# Net4CPC.net
KiCad netlist of a schematic drawn in EAGLE
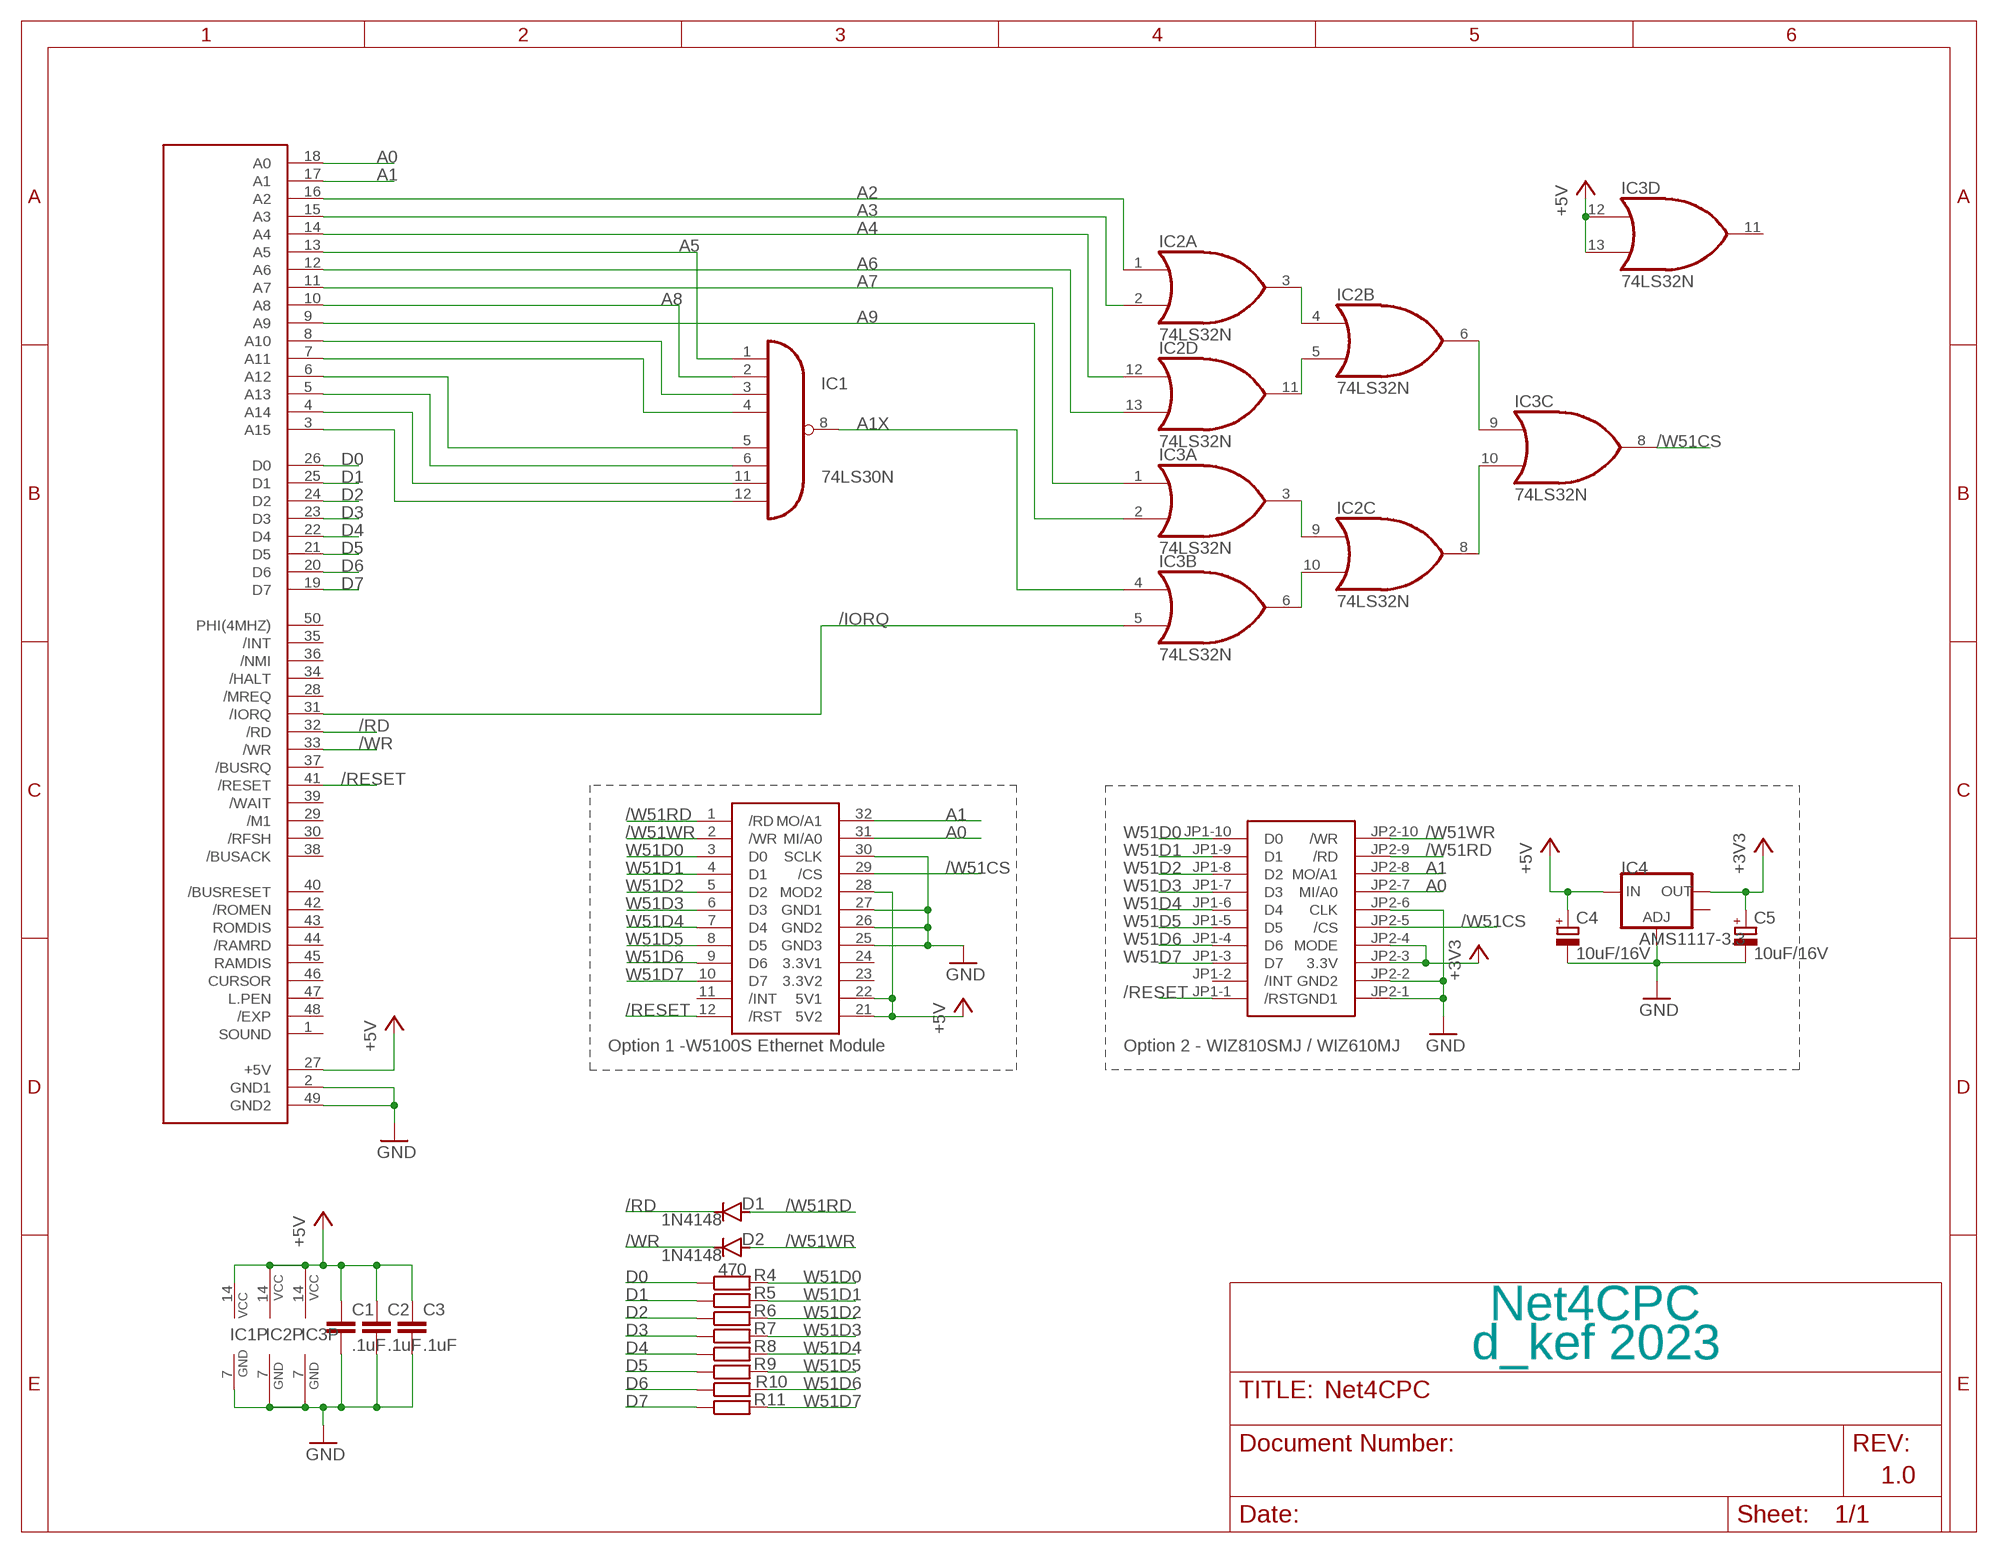
[diagram p0: schematic, sheet 1]

(export (version "E")
  (design (tool "Eeschema 10.0.6"))
  (components
    (comp (ref "C1")
      (value ".1uF")
      (footprint "eagle-import:C025-025X050")
      (libsource (lib "eagle-import") (part "C-EU025-025X050"))
    )
    (comp (ref "C2")
      (value ".1uF")
      (footprint "eagle-import:C025-025X050")
      (libsource (lib "eagle-import") (part "C-EU025-025X050"))
    )
    (comp (ref "C3")
      (value ".1uF")
      (footprint "eagle-import:C025-025X050")
      (libsource (lib "eagle-import") (part "C-EU025-025X050"))
    )
    (comp (ref "C4")
      (value "10uF/16V")
      (footprint "eagle-import:E5-6")
      (libsource (lib "eagle-import") (part "CPOL-EUE5-6"))
    )
    (comp (ref "C5")
      (value "10uF/16V")
      (footprint "eagle-import:E5-6")
      (libsource (lib "eagle-import") (part "CPOL-EUE5-6"))
    )
    (comp (ref "CON1")
      (value "CPCBUS")
      (footprint "eagle-import:2X25")
      (libsource (lib "eagle-import") (part "AMSTRAD_CPC_BUSP"))
    )
    (comp (ref "D1")
      (value "1N4148")
      (footprint "eagle-import:DO35-7")
      (libsource (lib "eagle-import") (part "1N4148DO35-7"))
    )
    (comp (ref "D2")
      (value "1N4148")
      (footprint "eagle-import:DO35-7")
      (libsource (lib "eagle-import") (part "1N4148DO35-7"))
    )
    (comp (ref "IC1")
      (value "74LS30N")
      (footprint "eagle-import:DIL14")
      (libsource (lib "eagle-import") (part "7430NHCT"))
    )
    (comp (ref "IC2")
      (value "74LS32N")
      (footprint "eagle-import:DIL14")
      (libsource (lib "eagle-import") (part "7432NLS"))
    )
    (comp (ref "IC3")
      (value "74LS32N")
      (footprint "eagle-import:DIL14")
      (libsource (lib "eagle-import") (part "7432NLS"))
    )
    (comp (ref "IC4")
      (value "AMS1117-3.3")
      (footprint "eagle-import:SOT223")
      (libsource (lib "eagle-import") (part "V_REG_LM1117SOT223"))
    )
    (comp (ref "R4")
      (value "470")
      (footprint "eagle-import:0204_7")
      (libsource (lib "eagle-import") (part "R-EU_0204/7"))
    )
    (comp (ref "R5")
      (value "470")
      (footprint "eagle-import:0204_7")
      (libsource (lib "eagle-import") (part "R-EU_0204/7"))
    )
    (comp (ref "R6")
      (value "470")
      (footprint "eagle-import:0204_7")
      (libsource (lib "eagle-import") (part "R-EU_0204/7"))
    )
    (comp (ref "R7")
      (value "470")
      (footprint "eagle-import:0204_7")
      (libsource (lib "eagle-import") (part "R-EU_0204/7"))
    )
    (comp (ref "R8")
      (value "470")
      (footprint "eagle-import:0204_7")
      (libsource (lib "eagle-import") (part "R-EU_0204/7"))
    )
    (comp (ref "R9")
      (value "470")
      (footprint "eagle-import:0204_7")
      (libsource (lib "eagle-import") (part "R-EU_0204/7"))
    )
    (comp (ref "R10")
      (value "470")
      (footprint "eagle-import:0204_7")
      (libsource (lib "eagle-import") (part "R-EU_0204/7"))
    )
    (comp (ref "R11")
      (value "470")
      (footprint "eagle-import:0204_7")
      (libsource (lib "eagle-import") (part "R-EU_0204/7"))
    )
    (comp (ref "W5100S-MODULE")
      (value "W5100S-NETWORK-MODULENO-NAMES")
      (footprint "eagle-import:W5100S-NETWORK-MODULE-NO-NAMES")
      (libsource (lib "eagle-import") (part "W5100S-NETWORK-MODULENO-NAMES"))
    )
    (comp (ref "WIZ810SMJ")
      (value "WIZ810SMJ-NETWORK-MODULENO-NAMES")
      (footprint "eagle-import:WIZ810SMJ-NETWORK-MODULE-NO-NAMES")
      (libsource (lib "eagle-import") (part "WIZ810SMJ-NETWORK-MODULENO-NAMES"))
    )
  )
  (nets
    (net (code "1") (name "+3V3") (class "Default")
      (node (ref "C5") (pin "+") (pinfunction "+_+") (pintype "passive"))
      (node (ref "IC4") (pin "2") (pinfunction "OUT_2") (pintype "output"))
      (node (ref "WIZ810SMJ") (pin "JP2-3") (pinfunction "3.3V_JP2-3") (pintype "power_in"))
      (node (ref "WIZ810SMJ") (pin "JP2-4") (pinfunction "MODE_JP2-4") (pintype "passive"))
    )
    (net (code "2") (name "+5V") (class "Default")
      (node (ref "C1") (pin "1") (pinfunction "1_1") (pintype "passive"))
      (node (ref "C2") (pin "1") (pinfunction "1_1") (pintype "passive"))
      (node (ref "C3") (pin "1") (pinfunction "1_1") (pintype "passive"))
      (node (ref "C4") (pin "+") (pinfunction "+_+") (pintype "passive"))
      (node (ref "CON1") (pin "27") (pinfunction "+5V_27") (pintype "bidirectional"))
      (node (ref "IC1") (pin "14") (pinfunction "VCC_14") (pintype "power_in"))
      (node (ref "IC2") (pin "14") (pinfunction "VCC_14") (pintype "power_in"))
      (node (ref "IC3") (pin "12") (pinfunction "I0_12") (pintype "input"))
      (node (ref "IC3") (pin "13") (pinfunction "I1_13") (pintype "input"))
      (node (ref "IC3") (pin "14") (pinfunction "VCC_14") (pintype "power_in"))
      (node (ref "IC4") (pin "3") (pinfunction "IN_3") (pintype "input"))
      (node (ref "W5100S-MODULE") (pin "21") (pinfunction "5V2_21") (pintype "power_in"))
      (node (ref "W5100S-MODULE") (pin "22") (pinfunction "5V1_22") (pintype "power_in"))
      (node (ref "W5100S-MODULE") (pin "28") (pinfunction "MOD2_28") (pintype "passive"))
    )
    (net (code "3") (name "/3.3V1") (class "Default")
      (node (ref "W5100S-MODULE") (pin "24") (pinfunction "3.3V1_24") (pintype "power_in"))
    )
    (net (code "4") (name "/3.3V2") (class "Default")
      (node (ref "W5100S-MODULE") (pin "23") (pinfunction "3.3V2_23") (pintype "power_in"))
    )
    (net (code "5") (name "/A0") (class "Default")
      (node (ref "CON1") (pin "18") (pinfunction "A0_18") (pintype "bidirectional"))
      (node (ref "W5100S-MODULE") (pin "31") (pinfunction "MI/A0_31") (pintype "input"))
      (node (ref "WIZ810SMJ") (pin "JP2-7") (pinfunction "MI/A0_JP2-7") (pintype "input"))
    )
    (net (code "6") (name "/A1") (class "Default")
      (node (ref "CON1") (pin "17") (pinfunction "A1_17") (pintype "bidirectional"))
      (node (ref "W5100S-MODULE") (pin "32") (pinfunction "MO/A1_32") (pintype "bidirectional"))
      (node (ref "WIZ810SMJ") (pin "JP2-8") (pinfunction "MO/A1_JP2-8") (pintype "bidirectional"))
    )
    (net (code "7") (name "/A1X") (class "Default")
      (node (ref "IC1") (pin "8") (pinfunction "O_8") (pintype "output"))
      (node (ref "IC3") (pin "4") (pinfunction "I0_4") (pintype "input"))
    )
    (net (code "8") (name "/A2") (class "Default")
      (node (ref "CON1") (pin "16") (pinfunction "A2_16") (pintype "bidirectional"))
      (node (ref "IC2") (pin "1") (pinfunction "I0_1") (pintype "input"))
    )
    (net (code "9") (name "/A3") (class "Default")
      (node (ref "CON1") (pin "15") (pinfunction "A3_15") (pintype "bidirectional"))
      (node (ref "IC2") (pin "2") (pinfunction "I1_2") (pintype "input"))
    )
    (net (code "10") (name "/A4") (class "Default")
      (node (ref "CON1") (pin "14") (pinfunction "A4_14") (pintype "bidirectional"))
      (node (ref "IC2") (pin "12") (pinfunction "I0_12") (pintype "input"))
    )
    (net (code "11") (name "/A5") (class "Default")
      (node (ref "CON1") (pin "13") (pinfunction "A5_13") (pintype "bidirectional"))
      (node (ref "IC1") (pin "1") (pinfunction "I0_1") (pintype "input"))
    )
    (net (code "12") (name "/A6") (class "Default")
      (node (ref "CON1") (pin "12") (pinfunction "A6_12") (pintype "bidirectional"))
      (node (ref "IC2") (pin "13") (pinfunction "I1_13") (pintype "input"))
    )
    (net (code "13") (name "/A7") (class "Default")
      (node (ref "CON1") (pin "11") (pinfunction "A7_11") (pintype "bidirectional"))
      (node (ref "IC3") (pin "1") (pinfunction "I0_1") (pintype "input"))
    )
    (net (code "14") (name "/A8") (class "Default")
      (node (ref "CON1") (pin "10") (pinfunction "A8_10") (pintype "bidirectional"))
      (node (ref "IC1") (pin "2") (pinfunction "I1_2") (pintype "input"))
    )
    (net (code "15") (name "/A9") (class "Default")
      (node (ref "CON1") (pin "9") (pinfunction "A9_9") (pintype "bidirectional"))
      (node (ref "IC3") (pin "2") (pinfunction "I1_2") (pintype "input"))
    )
    (net (code "16") (name "/D0") (class "Default")
      (node (ref "CON1") (pin "26") (pinfunction "D0_26") (pintype "bidirectional"))
      (node (ref "R4") (pin "1") (pinfunction "1_1") (pintype "passive"))
    )
    (net (code "17") (name "/D1") (class "Default")
      (node (ref "CON1") (pin "25") (pinfunction "D1_25") (pintype "bidirectional"))
      (node (ref "R5") (pin "1") (pinfunction "1_1") (pintype "passive"))
    )
    (net (code "18") (name "/D2") (class "Default")
      (node (ref "CON1") (pin "24") (pinfunction "D2_24") (pintype "bidirectional"))
      (node (ref "R6") (pin "1") (pinfunction "1_1") (pintype "passive"))
    )
    (net (code "19") (name "/D3") (class "Default")
      (node (ref "CON1") (pin "23") (pinfunction "D3_23") (pintype "bidirectional"))
      (node (ref "R7") (pin "1") (pinfunction "1_1") (pintype "passive"))
    )
    (net (code "20") (name "/D4") (class "Default")
      (node (ref "CON1") (pin "22") (pinfunction "D4_22") (pintype "bidirectional"))
      (node (ref "R8") (pin "1") (pinfunction "1_1") (pintype "passive"))
    )
    (net (code "21") (name "/D5") (class "Default")
      (node (ref "CON1") (pin "21") (pinfunction "D5_21") (pintype "bidirectional"))
      (node (ref "R9") (pin "1") (pinfunction "1_1") (pintype "passive"))
    )
    (net (code "22") (name "/D6") (class "Default")
      (node (ref "CON1") (pin "20") (pinfunction "D6_20") (pintype "bidirectional"))
      (node (ref "R10") (pin "1") (pinfunction "1_1") (pintype "passive"))
    )
    (net (code "23") (name "/D7") (class "Default")
      (node (ref "CON1") (pin "19") (pinfunction "D7_19") (pintype "bidirectional"))
      (node (ref "R11") (pin "1") (pinfunction "1_1") (pintype "passive"))
    )
    (net (code "24") (name "/W51D0") (class "Default")
      (node (ref "R4") (pin "2") (pinfunction "2_2") (pintype "passive"))
      (node (ref "W5100S-MODULE") (pin "3") (pinfunction "D0_3") (pintype "bidirectional"))
      (node (ref "WIZ810SMJ") (pin "JP1-10") (pinfunction "D0_JP1-10") (pintype "bidirectional"))
    )
    (net (code "25") (name "/W51D1") (class "Default")
      (node (ref "R5") (pin "2") (pinfunction "2_2") (pintype "passive"))
      (node (ref "W5100S-MODULE") (pin "4") (pinfunction "D1_4") (pintype "bidirectional"))
      (node (ref "WIZ810SMJ") (pin "JP1-9") (pinfunction "D1_JP1-9") (pintype "bidirectional"))
    )
    (net (code "26") (name "/W51D2") (class "Default")
      (node (ref "R6") (pin "2") (pinfunction "2_2") (pintype "passive"))
      (node (ref "W5100S-MODULE") (pin "5") (pinfunction "D2_5") (pintype "bidirectional"))
      (node (ref "WIZ810SMJ") (pin "JP1-8") (pinfunction "D2_JP1-8") (pintype "bidirectional"))
    )
    (net (code "27") (name "/W51D3") (class "Default")
      (node (ref "R7") (pin "2") (pinfunction "2_2") (pintype "passive"))
      (node (ref "W5100S-MODULE") (pin "6") (pinfunction "D3_6") (pintype "bidirectional"))
      (node (ref "WIZ810SMJ") (pin "JP1-7") (pinfunction "D3_JP1-7") (pintype "bidirectional"))
    )
    (net (code "28") (name "/W51D4") (class "Default")
      (node (ref "R8") (pin "2") (pinfunction "2_2") (pintype "passive"))
      (node (ref "W5100S-MODULE") (pin "7") (pinfunction "D4_7") (pintype "bidirectional"))
      (node (ref "WIZ810SMJ") (pin "JP1-6") (pinfunction "D4_JP1-6") (pintype "bidirectional"))
    )
    (net (code "29") (name "/W51D5") (class "Default")
      (node (ref "R9") (pin "2") (pinfunction "2_2") (pintype "passive"))
      (node (ref "W5100S-MODULE") (pin "8") (pinfunction "D5_8") (pintype "bidirectional"))
      (node (ref "WIZ810SMJ") (pin "JP1-5") (pinfunction "D5_JP1-5") (pintype "bidirectional"))
    )
    (net (code "30") (name "/W51D6") (class "Default")
      (node (ref "R10") (pin "2") (pinfunction "2_2") (pintype "passive"))
      (node (ref "W5100S-MODULE") (pin "9") (pinfunction "D6_9") (pintype "bidirectional"))
      (node (ref "WIZ810SMJ") (pin "JP1-4") (pinfunction "D6_JP1-4") (pintype "bidirectional"))
    )
    (net (code "31") (name "/W51D7") (class "Default")
      (node (ref "R11") (pin "2") (pinfunction "2_2") (pintype "passive"))
      (node (ref "W5100S-MODULE") (pin "10") (pinfunction "D7_10") (pintype "bidirectional"))
      (node (ref "WIZ810SMJ") (pin "JP1-3") (pinfunction "D7_JP1-3") (pintype "bidirectional"))
    )
    (net (code "32") (name "/{slash}IORQ") (class "Default")
      (node (ref "CON1") (pin "31") (pinfunction "/IORQ_31") (pintype "bidirectional"))
      (node (ref "IC3") (pin "5") (pinfunction "I1_5") (pintype "input"))
    )
    (net (code "33") (name "/{slash}RD") (class "Default")
      (node (ref "CON1") (pin "32") (pinfunction "/RD_32") (pintype "bidirectional"))
      (node (ref "D1") (pin "C") (pinfunction "C_C") (pintype "passive"))
    )
    (net (code "34") (name "/{slash}RESET") (class "Default")
      (node (ref "CON1") (pin "41") (pinfunction "/RESET_41") (pintype "bidirectional"))
      (node (ref "W5100S-MODULE") (pin "12") (pinfunction "/RST_12") (pintype "input"))
      (node (ref "WIZ810SMJ") (pin "JP1-1") (pinfunction "/RST_JP1-1") (pintype "input"))
    )
    (net (code "35") (name "/{slash}W51CS") (class "Default")
      (node (ref "IC3") (pin "8") (pinfunction "O_8") (pintype "output"))
      (node (ref "W5100S-MODULE") (pin "29") (pinfunction "/CS_29") (pintype "input"))
      (node (ref "WIZ810SMJ") (pin "JP2-5") (pinfunction "/CS_JP2-5") (pintype "input"))
    )
    (net (code "36") (name "/{slash}W51RD") (class "Default")
      (node (ref "D1") (pin "A") (pinfunction "A_A") (pintype "passive"))
      (node (ref "W5100S-MODULE") (pin "1") (pinfunction "/RD_1") (pintype "input"))
      (node (ref "WIZ810SMJ") (pin "JP2-9") (pinfunction "/RD_JP2-9") (pintype "input"))
    )
    (net (code "37") (name "/{slash}W51WR") (class "Default")
      (node (ref "D2") (pin "A") (pinfunction "A_A") (pintype "passive"))
      (node (ref "W5100S-MODULE") (pin "2") (pinfunction "/WR_2") (pintype "input"))
      (node (ref "WIZ810SMJ") (pin "JP2-10") (pinfunction "/WR_JP2-10") (pintype "input"))
    )
    (net (code "38") (name "/{slash}WR") (class "Default")
      (node (ref "CON1") (pin "33") (pinfunction "/WR_33") (pintype "bidirectional"))
      (node (ref "D2") (pin "C") (pinfunction "C_C") (pintype "passive"))
    )
    (net (code "39") (name "GND") (class "Default")
      (node (ref "C1") (pin "2") (pinfunction "2_2") (pintype "passive"))
      (node (ref "C2") (pin "2") (pinfunction "2_2") (pintype "passive"))
      (node (ref "C3") (pin "2") (pinfunction "2_2") (pintype "passive"))
      (node (ref "C4") (pin "-") (pinfunction "-_-") (pintype "passive"))
      (node (ref "C5") (pin "-") (pinfunction "-_-") (pintype "passive"))
      (node (ref "CON1") (pin "2") (pinfunction "GND1_2") (pintype "bidirectional"))
      (node (ref "CON1") (pin "49") (pinfunction "GND2_49") (pintype "bidirectional"))
      (node (ref "IC1") (pin "7") (pinfunction "GND_7") (pintype "power_in"))
      (node (ref "IC2") (pin "7") (pinfunction "GND_7") (pintype "power_in"))
      (node (ref "IC3") (pin "7") (pinfunction "GND_7") (pintype "power_in"))
      (node (ref "IC4") (pin "1") (pinfunction "ADJ_1") (pintype "input"))
      (node (ref "W5100S-MODULE") (pin "25") (pinfunction "GND3_25") (pintype "power_in"))
      (node (ref "W5100S-MODULE") (pin "26") (pinfunction "GND2_26") (pintype "power_in"))
      (node (ref "W5100S-MODULE") (pin "27") (pinfunction "GND1_27") (pintype "power_in"))
      (node (ref "W5100S-MODULE") (pin "30") (pinfunction "SCLK_30") (pintype "output"))
      (node (ref "WIZ810SMJ") (pin "JP2-1") (pinfunction "GND1_JP2-1") (pintype "power_in"))
      (node (ref "WIZ810SMJ") (pin "JP2-2") (pinfunction "GND2_JP2-2") (pintype "power_in"))
      (node (ref "WIZ810SMJ") (pin "JP2-6") (pinfunction "CLK_JP2-6") (pintype "output"))
    )
    (net (code "40") (name "Net-(CON1-A10)") (class "Default")
      (node (ref "CON1") (pin "8") (pinfunction "A10_8") (pintype "bidirectional"))
      (node (ref "IC1") (pin "3") (pinfunction "I2_3") (pintype "input"))
    )
    (net (code "41") (name "Net-(CON1-A11)") (class "Default")
      (node (ref "CON1") (pin "7") (pinfunction "A11_7") (pintype "bidirectional"))
      (node (ref "IC1") (pin "4") (pinfunction "I3_4") (pintype "input"))
    )
    (net (code "42") (name "Net-(CON1-A12)") (class "Default")
      (node (ref "CON1") (pin "6") (pinfunction "A12_6") (pintype "bidirectional"))
      (node (ref "IC1") (pin "5") (pinfunction "I4_5") (pintype "input"))
    )
    (net (code "43") (name "Net-(CON1-A13)") (class "Default")
      (node (ref "CON1") (pin "5") (pinfunction "A13_5") (pintype "bidirectional"))
      (node (ref "IC1") (pin "6") (pinfunction "I5_6") (pintype "input"))
    )
    (net (code "44") (name "Net-(CON1-A14)") (class "Default")
      (node (ref "CON1") (pin "4") (pinfunction "A14_4") (pintype "bidirectional"))
      (node (ref "IC1") (pin "11") (pinfunction "I6_11") (pintype "input"))
    )
    (net (code "45") (name "Net-(CON1-A15)") (class "Default")
      (node (ref "CON1") (pin "3") (pinfunction "A15_3") (pintype "bidirectional"))
      (node (ref "IC1") (pin "12") (pinfunction "I7_12") (pintype "input"))
    )
    (net (code "46") (name "Net-(IC2A-O)") (class "Default")
      (node (ref "IC2") (pin "3") (pinfunction "O_3") (pintype "output"))
      (node (ref "IC2") (pin "4") (pinfunction "I0_4") (pintype "input"))
    )
    (net (code "47") (name "Net-(IC2B-I1)") (class "Default")
      (node (ref "IC2") (pin "11") (pinfunction "O_11") (pintype "output"))
      (node (ref "IC2") (pin "5") (pinfunction "I1_5") (pintype "input"))
    )
    (net (code "48") (name "Net-(IC2B-O)") (class "Default")
      (node (ref "IC2") (pin "6") (pinfunction "O_6") (pintype "output"))
      (node (ref "IC3") (pin "9") (pinfunction "I0_9") (pintype "input"))
    )
    (net (code "49") (name "Net-(IC2C-I0)") (class "Default")
      (node (ref "IC2") (pin "9") (pinfunction "I0_9") (pintype "input"))
      (node (ref "IC3") (pin "3") (pinfunction "O_3") (pintype "output"))
    )
    (net (code "50") (name "Net-(IC2C-I1)") (class "Default")
      (node (ref "IC2") (pin "10") (pinfunction "I1_10") (pintype "input"))
      (node (ref "IC3") (pin "6") (pinfunction "O_6") (pintype "output"))
    )
    (net (code "51") (name "Net-(IC2C-O)") (class "Default")
      (node (ref "IC2") (pin "8") (pinfunction "O_8") (pintype "output"))
      (node (ref "IC3") (pin "10") (pinfunction "I1_10") (pintype "input"))
    )
    (net (code "52") (name "unconnected-(CON1-CURSOR-Pad46)") (class "Default")
      (node (ref "CON1") (pin "46") (pinfunction "CURSOR_46") (pintype "bidirectional"))
    )
    (net (code "53") (name "unconnected-(CON1-L.PEN-Pad47)") (class "Default")
      (node (ref "CON1") (pin "47") (pinfunction "L.PEN_47") (pintype "bidirectional"))
    )
    (net (code "54") (name "unconnected-(CON1-PHI(4MHZ)-Pad50)") (class "Default")
      (node (ref "CON1") (pin "50") (pinfunction "PHI(4MHZ)_50") (pintype "bidirectional"))
    )
    (net (code "55") (name "unconnected-(CON1-RAMDIS-Pad45)") (class "Default")
      (node (ref "CON1") (pin "45") (pinfunction "RAMDIS_45") (pintype "bidirectional"))
    )
    (net (code "56") (name "unconnected-(CON1-ROMDIS-Pad43)") (class "Default")
      (node (ref "CON1") (pin "43") (pinfunction "ROMDIS_43") (pintype "bidirectional"))
    )
    (net (code "57") (name "unconnected-(CON1-SOUND-Pad1)") (class "Default")
      (node (ref "CON1") (pin "1") (pinfunction "SOUND_1") (pintype "bidirectional"))
    )
    (net (code "58") (name "unconnected-(CON1-{slash}BUSACK-Pad38)") (class "Default")
      (node (ref "CON1") (pin "38") (pinfunction "/BUSACK_38") (pintype "bidirectional"))
    )
    (net (code "59") (name "unconnected-(CON1-{slash}BUSRESET-Pad40)") (class "Default")
      (node (ref "CON1") (pin "40") (pinfunction "/BUSRESET_40") (pintype "bidirectional"))
    )
    (net (code "60") (name "unconnected-(CON1-{slash}BUSRQ-Pad37)") (class "Default")
      (node (ref "CON1") (pin "37") (pinfunction "/BUSRQ_37") (pintype "bidirectional"))
    )
    (net (code "61") (name "unconnected-(CON1-{slash}EXP-Pad48)") (class "Default")
      (node (ref "CON1") (pin "48") (pinfunction "/EXP_48") (pintype "bidirectional"))
    )
    (net (code "62") (name "unconnected-(CON1-{slash}HALT-Pad34)") (class "Default")
      (node (ref "CON1") (pin "34") (pinfunction "/HALT_34") (pintype "bidirectional"))
    )
    (net (code "63") (name "unconnected-(CON1-{slash}INT-Pad35)") (class "Default")
      (node (ref "CON1") (pin "35") (pinfunction "/INT_35") (pintype "bidirectional"))
    )
    (net (code "64") (name "unconnected-(CON1-{slash}M1-Pad29)") (class "Default")
      (node (ref "CON1") (pin "29") (pinfunction "/M1_29") (pintype "bidirectional"))
    )
    (net (code "65") (name "unconnected-(CON1-{slash}MREQ-Pad28)") (class "Default")
      (node (ref "CON1") (pin "28") (pinfunction "/MREQ_28") (pintype "bidirectional"))
    )
    (net (code "66") (name "unconnected-(CON1-{slash}NMI-Pad36)") (class "Default")
      (node (ref "CON1") (pin "36") (pinfunction "/NMI_36") (pintype "bidirectional"))
    )
    (net (code "67") (name "unconnected-(CON1-{slash}RAMRD-Pad44)") (class "Default")
      (node (ref "CON1") (pin "44") (pinfunction "/RAMRD_44") (pintype "bidirectional"))
    )
    (net (code "68") (name "unconnected-(CON1-{slash}RFSH-Pad30)") (class "Default")
      (node (ref "CON1") (pin "30") (pinfunction "/RFSH_30") (pintype "bidirectional"))
    )
    (net (code "69") (name "unconnected-(CON1-{slash}ROMEN-Pad42)") (class "Default")
      (node (ref "CON1") (pin "42") (pinfunction "/ROMEN_42") (pintype "bidirectional"))
    )
    (net (code "70") (name "unconnected-(CON1-{slash}WAIT-Pad39)") (class "Default")
      (node (ref "CON1") (pin "39") (pinfunction "/WAIT_39") (pintype "bidirectional"))
    )
    (net (code "71") (name "unconnected-(IC3D-O-Pad11)") (class "Default")
      (node (ref "IC3") (pin "11") (pinfunction "O_11") (pintype "output"))
    )
    (net (code "72") (name "unconnected-(IC4-OUT-Pad4)") (class "Default")
      (node (ref "IC4") (pin "4") (pinfunction "OUT_4") (pintype "output"))
    )
    (net (code "73") (name "unconnected-(W5100S-MODULE-{slash}INT-Pad11)") (class "Default")
      (node (ref "W5100S-MODULE") (pin "11") (pinfunction "/INT_11") (pintype "output"))
    )
    (net (code "74") (name "unconnected-(WIZ810SMJ-{slash}INT-PadJP1-2)") (class "Default")
      (node (ref "WIZ810SMJ") (pin "JP1-2") (pinfunction "/INT_JP1-2") (pintype "output"))
    )
  )
)
